# talkie.net
KiCad netlist of a schematic drawn in EAGLE
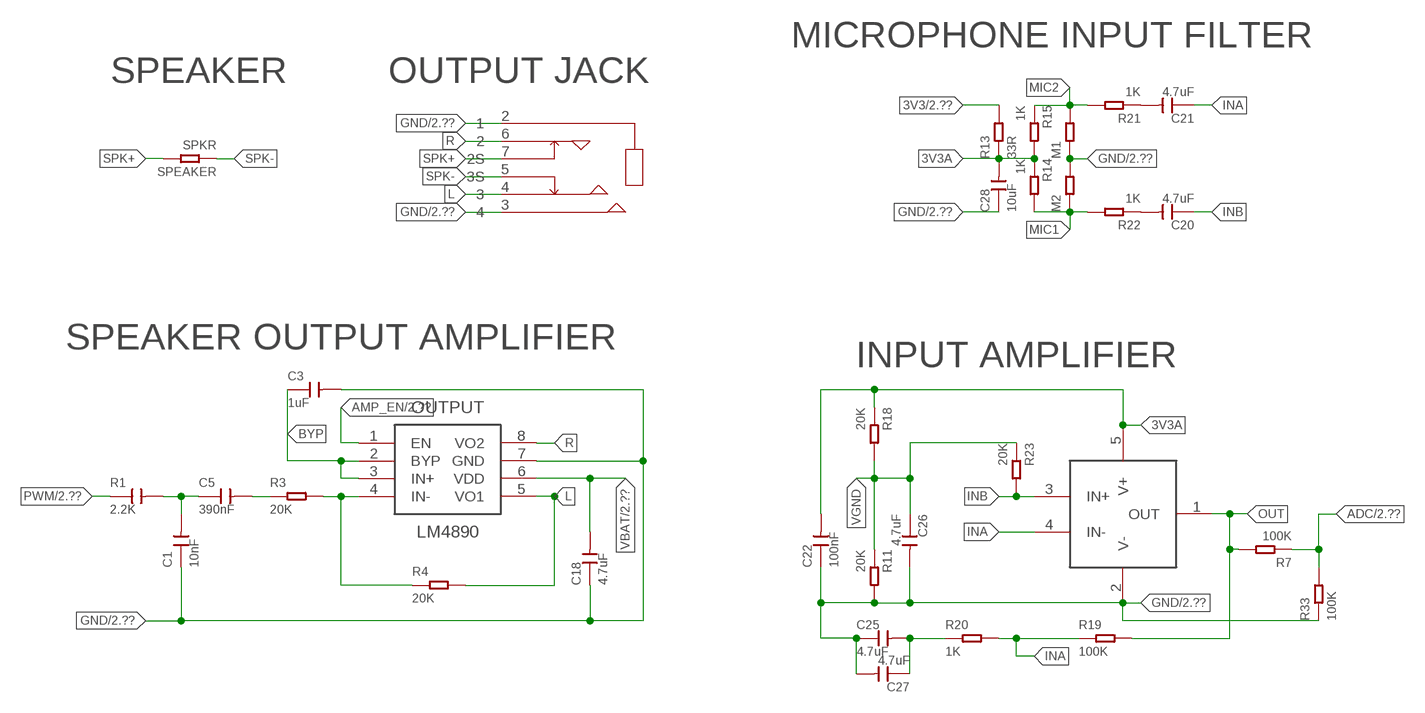
[diagram p0: schematic, sheet 1]
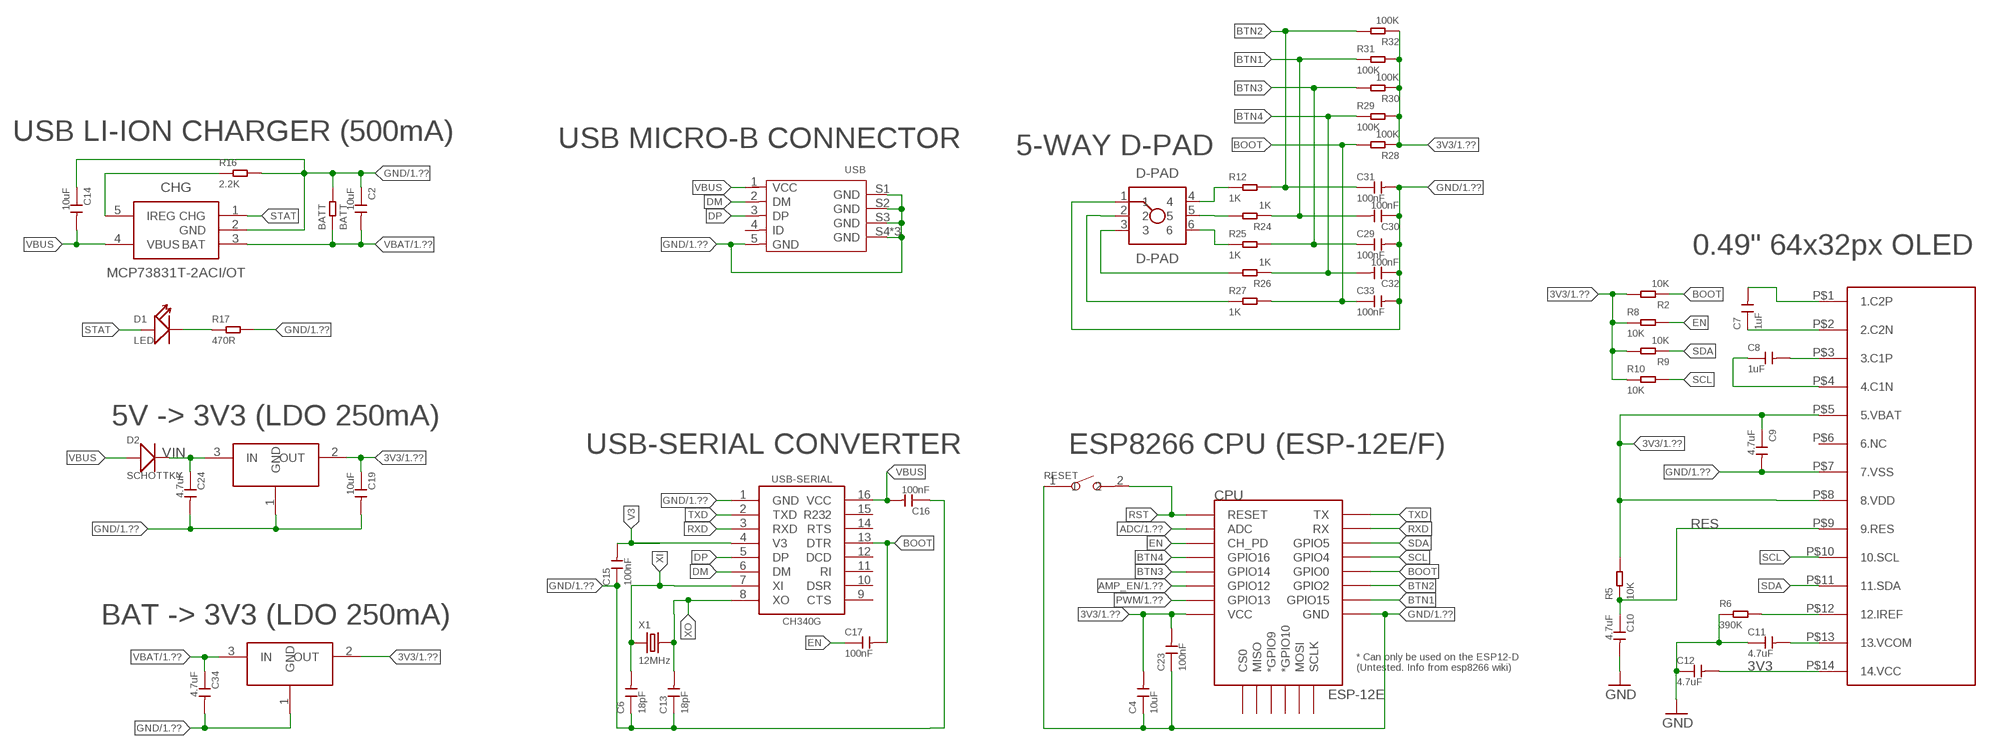
[diagram p1: schematic, sheet 2]

(export (version "E")
  (design (tool "Eeschema 10.0.6"))
  (components
    (comp (ref "C1")
      (value "10nF")
      (footprint "eagle-import:C0402")
      (fields (field (name "MPN") "CC0402KRX7R9BB103"))
      (libsource (lib "eagle-import") (part "CERAMIC-10NF-50V-10%-X7R(0402)"))
    )
    (comp (ref "C3")
      (value "1uF")
      (footprint "eagle-import:C0402")
      (fields (field (name "MPN") "CC0402KRX5R6BB105"))
      (libsource (lib "eagle-import") (part "CERAMIC-1UF-10V-10%-X5R(0402)"))
    )
    (comp (ref "C5")
      (value "390nF")
      (footprint "eagle-import:C0402")
      (fields (field (name "MPN") "CC0402KRX5R6BB474"))
      (libsource (lib "eagle-import") (part "CERAMIC-470NF-10V-10%-X5R(0402)"))
    )
    (comp (ref "C18")
      (value "4.7uF")
      (footprint "eagle-import:C0402")
      (fields (field (name "MPN") "CC0402MRX5R5BB475"))
      (libsource (lib "eagle-import") (part "CERAMIC-4.7UF-6.3V-20%-X5R(0402)"))
    )
    (comp (ref "C20")
      (value "4.7uF")
      (footprint "eagle-import:C0402")
      (fields (field (name "MPN") "CC0402MRX5R5BB475"))
      (libsource (lib "eagle-import") (part "CERAMIC-4.7UF-6.3V-20%-X5R(0402)"))
    )
    (comp (ref "C21")
      (value "4.7uF")
      (footprint "eagle-import:C0402")
      (fields (field (name "MPN") "CC0402MRX5R5BB475"))
      (libsource (lib "eagle-import") (part "CERAMIC-4.7UF-6.3V-20%-X5R(0402)"))
    )
    (comp (ref "C22")
      (value "100nF")
      (footprint "eagle-import:C0402")
      (fields (field (name "MPN") "CC0402KRX7R8BB104"))
      (libsource (lib "eagle-import") (part "CERAMIC-100NF-25V-10%-X7R(0402)"))
    )
    (comp (ref "C25")
      (value "4.7uF")
      (footprint "eagle-import:C0402")
      (fields (field (name "MPN") "CC0402MRX5R5BB475"))
      (libsource (lib "eagle-import") (part "CERAMIC-4.7UF-6.3V-20%-X5R(0402)"))
    )
    (comp (ref "C26")
      (value "4.7uF")
      (footprint "eagle-import:C0402")
      (fields (field (name "MPN") "CC0402MRX5R5BB475"))
      (libsource (lib "eagle-import") (part "CERAMIC-4.7UF-6.3V-20%-X5R(0402)"))
    )
    (comp (ref "C27")
      (value "4.7uF")
      (footprint "eagle-import:C0402")
      (fields (field (name "MPN") "CC0402MRX5R5BB475"))
      (libsource (lib "eagle-import") (part "CERAMIC-4.7UF-6.3V-20%-X5R(0402)"))
    )
    (comp (ref "C28")
      (value "10uF")
      (footprint "eagle-import:C0603")
      (fields (field (name "MPN") "CC0603KRX5R6BB106"))
      (libsource (lib "eagle-import") (part "CERAMIC-10UF-10V-10%-X5R(0603)"))
    )
    (comp (ref "JACK")
      (value "PJ-342")
      (footprint "eagle-import:PJ-342-6P")
      (libsource (lib "eagle-import") (part "PJ-342"))
    )
    (comp (ref "M1")
      (value "RES-1206")
      (footprint "eagle-import:R1206")
      (libsource (lib "eagle-import") (part "RES-1206"))
    )
    (comp (ref "M2")
      (value "RES-1206")
      (footprint "eagle-import:R1206")
      (libsource (lib "eagle-import") (part "RES-1206"))
    )
    (comp (ref "OUTPUT")
      (value "LM4890")
      (footprint "eagle-import:8-MSOP")
      (libsource (lib "eagle-import") (part "LM4890"))
    )
    (comp (ref "PREAMP")
      (value "MCP6001UT-I")
      (footprint "eagle-import:SOT-23-5")
      (libsource (lib "eagle-import") (part "MCP6001UT-I"))
    )
    (comp (ref "R1")
      (value "2.2K")
      (footprint "eagle-import:C0402")
      (fields (field (name "MPN") "CC0402KRX7R9BB103"))
      (libsource (lib "eagle-import") (part "CERAMIC-10NF-50V-10%-X7R(0402)"))
    )
    (comp (ref "R3")
      (value "20K")
      (footprint "eagle-import:R0402")
      (libsource (lib "eagle-import") (part "RES-0402"))
    )
    (comp (ref "R4")
      (value "20K")
      (footprint "eagle-import:R0402")
      (libsource (lib "eagle-import") (part "RES-0402"))
    )
    (comp (ref "R7")
      (value "100K")
      (footprint "eagle-import:R0402")
      (fields (field (name "MPN") "RC0402FR-07100KL"))
      (libsource (lib "eagle-import") (part "SMD-RES-100K-1%-1/16W(0402)"))
    )
    (comp (ref "R11")
      (value "20K")
      (footprint "eagle-import:R0402")
      (libsource (lib "eagle-import") (part "RES-0402"))
    )
    (comp (ref "R13")
      (value "33R")
      (footprint "eagle-import:R0402")
      (fields (field (name "MPN") "RC0402FR-0733RL"))
      (libsource (lib "eagle-import") (part "SMD-RES-33R-1%-1/16W(0402)"))
    )
    (comp (ref "R14")
      (value "1K")
      (footprint "eagle-import:R0402")
      (fields (field (name "MPN") "RC0402JR-071K5L"))
      (libsource (lib "eagle-import") (part "SMD-RES-1.5K-5%-1/16W(0402)"))
    )
    (comp (ref "R15")
      (value "1K")
      (footprint "eagle-import:R0402")
      (fields (field (name "MPN") "RC0402JR-071K5L"))
      (libsource (lib "eagle-import") (part "SMD-RES-1.5K-5%-1/16W(0402)"))
    )
    (comp (ref "R18")
      (value "20K")
      (footprint "eagle-import:R0402")
      (libsource (lib "eagle-import") (part "RES-0402"))
    )
    (comp (ref "R19")
      (value "100K")
      (footprint "eagle-import:R0402")
      (fields (field (name "MPN") "RC0402FR-07100KL"))
      (libsource (lib "eagle-import") (part "SMD-RES-100K-1%-1/16W(0402)"))
    )
    (comp (ref "R20")
      (value "1K")
      (footprint "eagle-import:R0402")
      (fields (field (name "MPN") "RC0402JR-071KL"))
      (libsource (lib "eagle-import") (part "SMD-RES-1K-5%-1/16W(0402)"))
    )
    (comp (ref "R21")
      (value "1K")
      (footprint "eagle-import:R0402")
      (fields (field (name "MPN") "RC0402JR-071K5L"))
      (libsource (lib "eagle-import") (part "SMD-RES-1.5K-5%-1/16W(0402)"))
    )
    (comp (ref "R22")
      (value "1K")
      (footprint "eagle-import:R0402")
      (fields (field (name "MPN") "RC0402JR-071K5L"))
      (libsource (lib "eagle-import") (part "SMD-RES-1.5K-5%-1/16W(0402)"))
    )
    (comp (ref "R23")
      (value "20K")
      (footprint "eagle-import:R0402")
      (libsource (lib "eagle-import") (part "RES-0402"))
    )
    (comp (ref "R33")
      (value "100K")
      (footprint "eagle-import:R0402")
      (fields (field (name "MPN") "RC0402FR-07100KL"))
      (libsource (lib "eagle-import") (part "SMD-RES-100K-1%-1/16W(0402)"))
    )
    (comp (ref "SPEAKER")
      (value "SPKR")
      (footprint "eagle-import:R1206")
      (libsource (lib "eagle-import") (part "RES-1206"))
    )
    (comp (ref "BATT")
      (value "BATT")
      (footprint "eagle-import:R1206")
      (libsource (lib "eagle-import") (part "RES-1206"))
    )
    (comp (ref "C2")
      (value "10uF")
      (footprint "eagle-import:C0603")
      (fields (field (name "MPN") "CC0603KRX5R6BB106"))
      (libsource (lib "eagle-import") (part "CERAMIC-10UF-10V-10%-X5R(0603)"))
    )
    (comp (ref "C4")
      (value "10uF")
      (footprint "eagle-import:C0603")
      (fields (field (name "MPN") "CC0603KRX5R6BB475"))
      (libsource (lib "eagle-import") (part "CERAMIC-4.7UF-10V-10%-X5R(0603)"))
    )
    (comp (ref "C6")
      (value "18pF")
      (footprint "eagle-import:C0402")
      (fields (field (name "MPN") "CC0402JRNPO9BN180"))
      (libsource (lib "eagle-import") (part "CERAMIC-18PF-50V-5%-NPO(0402)"))
    )
    (comp (ref "C7")
      (value "1uF")
      (footprint "eagle-import:C0402")
      (fields (field (name "MPN") "CC0402KRX5R6BB105"))
      (libsource (lib "eagle-import") (part "CERAMIC-1UF-10V-10%-X5R(0402)"))
    )
    (comp (ref "C8")
      (value "1uF")
      (footprint "eagle-import:C0402")
      (fields (field (name "MPN") "CC0402KRX5R6BB105"))
      (libsource (lib "eagle-import") (part "CERAMIC-1UF-10V-10%-X5R(0402)"))
    )
    (comp (ref "C9")
      (value "4.7uF")
      (footprint "eagle-import:C0402")
      (fields (field (name "MPN") "CC0402MRX5R5BB475"))
      (libsource (lib "eagle-import") (part "CERAMIC-4.7UF-6.3V-20%-X5R(0402)"))
    )
    (comp (ref "C10")
      (value "4.7uF")
      (footprint "eagle-import:C0402")
      (fields (field (name "MPN") "CC0402MRX5R5BB475"))
      (libsource (lib "eagle-import") (part "CERAMIC-4.7UF-6.3V-20%-X5R(0402)"))
    )
    (comp (ref "C11")
      (value "4.7uF")
      (footprint "eagle-import:C0402")
      (fields (field (name "MPN") "CC0402MRX5R5BB475"))
      (libsource (lib "eagle-import") (part "CERAMIC-4.7UF-6.3V-20%-X5R(0402)"))
    )
    (comp (ref "C12")
      (value "4.7uF")
      (footprint "eagle-import:C0402")
      (fields (field (name "MPN") "CC0402MRX5R5BB475"))
      (libsource (lib "eagle-import") (part "CERAMIC-4.7UF-6.3V-20%-X5R(0402)"))
    )
    (comp (ref "C13")
      (value "18pF")
      (footprint "eagle-import:C0402")
      (fields (field (name "MPN") "CC0402JRNPO9BN180"))
      (libsource (lib "eagle-import") (part "CERAMIC-18PF-50V-5%-NPO(0402)"))
    )
    (comp (ref "C14")
      (value "10uF")
      (footprint "eagle-import:C0603")
      (fields (field (name "MPN") "CC0603KRX5R6BB106"))
      (libsource (lib "eagle-import") (part "CERAMIC-10UF-10V-10%-X5R(0603)"))
    )
    (comp (ref "C15")
      (value "100nF")
      (footprint "eagle-import:C0402")
      (fields (field (name "MPN") "CC0402KRX7R8BB104"))
      (libsource (lib "eagle-import") (part "CERAMIC-100NF-25V-10%-X7R(0402)"))
    )
    (comp (ref "C16")
      (value "100nF")
      (footprint "eagle-import:C0402")
      (fields (field (name "MPN") "CC0402KRX7R8BB104"))
      (libsource (lib "eagle-import") (part "CERAMIC-100NF-25V-10%-X7R(0402)"))
    )
    (comp (ref "C17")
      (value "100nF")
      (footprint "eagle-import:C0402")
      (fields (field (name "MPN") "CC0402KRX7R8BB104"))
      (libsource (lib "eagle-import") (part "CERAMIC-100NF-25V-10%-X7R(0402)"))
    )
    (comp (ref "C19")
      (value "10uF")
      (footprint "eagle-import:C0603")
      (fields (field (name "MPN") "CC0603KRX5R6BB106"))
      (libsource (lib "eagle-import") (part "CERAMIC-10UF-10V-10%-X5R(0603)"))
    )
    (comp (ref "C23")
      (value "100nF")
      (footprint "eagle-import:C0402")
      (fields (field (name "MPN") "CC0402KRX7R8BB104"))
      (libsource (lib "eagle-import") (part "CERAMIC-100NF-25V-10%-X7R(0402)"))
    )
    (comp (ref "C24")
      (value "4.7uF")
      (footprint "eagle-import:C0402")
      (fields (field (name "MPN") "CC0402MRX5R5BB475"))
      (libsource (lib "eagle-import") (part "CERAMIC-4.7UF-6.3V-20%-X5R(0402)"))
    )
    (comp (ref "C29")
      (value "100nF")
      (footprint "eagle-import:C0402")
      (fields (field (name "MPN") "CC0402KRX7R8BB104"))
      (libsource (lib "eagle-import") (part "CERAMIC-100NF-25V-10%-X7R(0402)"))
    )
    (comp (ref "C30")
      (value "100nF")
      (footprint "eagle-import:C0402")
      (fields (field (name "MPN") "CC0402KRX7R8BB104"))
      (libsource (lib "eagle-import") (part "CERAMIC-100NF-25V-10%-X7R(0402)"))
    )
    (comp (ref "C31")
      (value "100nF")
      (footprint "eagle-import:C0402")
      (fields (field (name "MPN") "CC0402KRX7R8BB104"))
      (libsource (lib "eagle-import") (part "CERAMIC-100NF-25V-10%-X7R(0402)"))
    )
    (comp (ref "C32")
      (value "100nF")
      (footprint "eagle-import:C0402")
      (fields (field (name "MPN") "CC0402KRX7R8BB104"))
      (libsource (lib "eagle-import") (part "CERAMIC-100NF-25V-10%-X7R(0402)"))
    )
    (comp (ref "C33")
      (value "100nF")
      (footprint "eagle-import:C0402")
      (fields (field (name "MPN") "CC0402KRX7R8BB104"))
      (libsource (lib "eagle-import") (part "CERAMIC-100NF-25V-10%-X7R(0402)"))
    )
    (comp (ref "C34")
      (value "4.7uF")
      (footprint "eagle-import:C0402")
      (fields (field (name "MPN") "CC0402MRX5R5BB475"))
      (libsource (lib "eagle-import") (part "CERAMIC-4.7UF-6.3V-20%-X5R(0402)"))
    )
    (comp (ref "CHG")
      (value "MCP73831T-2ACI/OT")
      (footprint "eagle-import:SOT-23-5")
      (libsource (lib "eagle-import") (part "MCP73831T-2ACI/OT"))
    )
    (comp (ref "CPU")
      (value "ESP-12E")
      (footprint "eagle-import:ESP12E-SMD")
      (libsource (lib "eagle-import") (part "ESP12ESMD"))
    )
    (comp (ref "D-PAD")
      (value "D-PAD")
      (footprint "eagle-import:DPAD-10X10")
      (libsource (lib "eagle-import") (part "D-PAD"))
    )
    (comp (ref "D1")
      (value "LED")
      (footprint "eagle-import:LED-0402")
      (fields (field (name "MPN") "16-219A/T2D-AR2T1QY/3T"))
      (libsource (lib "eagle-import") (part "SMD-LED-YELLOW-DIFFUSED-PURE-WHITE(0402)"))
    )
    (comp (ref "D2")
      (value "SCHOTTKY")
      (footprint "eagle-import:SOD-123")
      (fields (field (name "MPN") "MBR0520LT1G"))
      (libsource (lib "eagle-import") (part "SMD-DIODE-SCHOTTKY-20V-500MA(SOD-123)"))
    )
    (comp (ref "LDO1")
      (value "MCP1700T")
      (footprint "eagle-import:SOT-23-3")
      (libsource (lib "eagle-import") (part "MCP1700T"))
    )
    (comp (ref "LDO2")
      (value "MCP1700T-3302E")
      (footprint "eagle-import:SOT-23-3")
      (libsource (lib "eagle-import") (part "MCP1700T"))
    )
    (comp (ref "OLED")
      (value "ER-OLED0.49")
      (footprint "eagle-import:ER-OLED0.49")
      (libsource (lib "eagle-import") (part "ER-OLED0.49"))
    )
    (comp (ref "R2")
      (value "10K")
      (footprint "eagle-import:R0402")
      (libsource (lib "eagle-import") (part "RES-0402"))
    )
    (comp (ref "R5")
      (value "10K")
      (footprint "eagle-import:R0402")
      (libsource (lib "eagle-import") (part "RES-0402"))
    )
    (comp (ref "R6")
      (value "390K")
      (footprint "eagle-import:R0402")
      (libsource (lib "eagle-import") (part "RES-0402"))
    )
    (comp (ref "R8")
      (value "10K")
      (footprint "eagle-import:R0402")
      (libsource (lib "eagle-import") (part "RES-0402"))
    )
    (comp (ref "R9")
      (value "10K")
      (footprint "eagle-import:R0402")
      (libsource (lib "eagle-import") (part "RES-0402"))
    )
    (comp (ref "R10")
      (value "10K")
      (footprint "eagle-import:R0402")
      (libsource (lib "eagle-import") (part "RES-0402"))
    )
    (comp (ref "R12")
      (value "1K")
      (footprint "eagle-import:R0402")
      (fields (field (name "MPN") "RC0402JR-071K5L"))
      (libsource (lib "eagle-import") (part "SMD-RES-1.5K-5%-1/16W(0402)"))
    )
    (comp (ref "R16")
      (value "2.2K")
      (footprint "eagle-import:R0402")
      (fields (field (name "MPN") "RC0402JR-072K2L"))
      (libsource (lib "eagle-import") (part "SMD-RES-2.2K-5%-1/16W(0402)"))
    )
    (comp (ref "R17")
      (value "470R")
      (footprint "eagle-import:R0402")
      (fields (field (name "MPN") "RC0402FR-07470RL"))
      (libsource (lib "eagle-import") (part "SMD-RES-470R-1%-1/16W(0402)"))
    )
    (comp (ref "R24")
      (value "1K")
      (footprint "eagle-import:R0402")
      (fields (field (name "MPN") "RC0402JR-071K5L"))
      (libsource (lib "eagle-import") (part "SMD-RES-1.5K-5%-1/16W(0402)"))
    )
    (comp (ref "R25")
      (value "1K")
      (footprint "eagle-import:R0402")
      (fields (field (name "MPN") "RC0402JR-071K5L"))
      (libsource (lib "eagle-import") (part "SMD-RES-1.5K-5%-1/16W(0402)"))
    )
    (comp (ref "R26")
      (value "1K")
      (footprint "eagle-import:R0402")
      (fields (field (name "MPN") "RC0402JR-071K5L"))
      (libsource (lib "eagle-import") (part "SMD-RES-1.5K-5%-1/16W(0402)"))
    )
    (comp (ref "R27")
      (value "1K")
      (footprint "eagle-import:R0402")
      (fields (field (name "MPN") "RC0402JR-071K5L"))
      (libsource (lib "eagle-import") (part "SMD-RES-1.5K-5%-1/16W(0402)"))
    )
    (comp (ref "R28")
      (value "100K")
      (footprint "eagle-import:R0402")
      (fields (field (name "MPN") "RC0402FR-07100KL"))
      (libsource (lib "eagle-import") (part "SMD-RES-100K-1%-1/16W(0402)"))
    )
    (comp (ref "R29")
      (value "100K")
      (footprint "eagle-import:R0402")
      (fields (field (name "MPN") "RC0402FR-07100KL"))
      (libsource (lib "eagle-import") (part "SMD-RES-100K-1%-1/16W(0402)"))
    )
    (comp (ref "R30")
      (value "100K")
      (footprint "eagle-import:R0402")
      (fields (field (name "MPN") "RC0402FR-07100KL"))
      (libsource (lib "eagle-import") (part "SMD-RES-100K-1%-1/16W(0402)"))
    )
    (comp (ref "R31")
      (value "100K")
      (footprint "eagle-import:R0402")
      (fields (field (name "MPN") "RC0402FR-07100KL"))
      (libsource (lib "eagle-import") (part "SMD-RES-100K-1%-1/16W(0402)"))
    )
    (comp (ref "R32")
      (value "100K")
      (footprint "eagle-import:R0402")
      (fields (field (name "MPN") "RC0402FR-07100KL"))
      (libsource (lib "eagle-import") (part "SMD-RES-100K-1%-1/16W(0402)"))
    )
    (comp (ref "RESET")
      (value "SMD-BUTTON(2P-3.0X2.5X1.2+0.4MM)-B3U-1000P-2P-SMD")
      (footprint "eagle-import:SW2-2.6-3.0X2.5X1.2+0.4MM")
      (libsource (lib "eagle-import") (part "SMD-BUTTON(2P-3.0X2.5X1.2+0.4MM)-B3U-1000P-2P-SMD"))
    )
    (comp (ref "USB")
      (value "MICRO-USB-SMD-B-WITHOUT-POST-W/P(ST-USB-001G)")
      (footprint "eagle-import:MICRO-USB5+4P-SMD-0.65-B")
      (fields (field (name "MPN") "ST-USB-001G"))
      (libsource (lib "eagle-import") (part "MICRO-USB-SMD-B-WITHOUT-POST-W/P(ST-USB-001G)"))
    )
    (comp (ref "USB-SERIAL")
      (value "CH340G")
      (footprint "eagle-import:16-SSOP")
      (libsource (lib "eagle-import") (part "CH340G"))
    )
    (comp (ref "X1")
      (value "12MHz")
      (footprint "eagle-import:X4-SMD-3.2X2.5X0.7MM")
      (libsource (lib "eagle-import") (part "CRYSTAL'3225'"))
    )
  )
  (nets
    (net (code "1") (name "3V3") (class "Default")
      (node (ref "C12") (pin "2") (pinfunction "2_2") (pintype "passive"))
      (node (ref "C19") (pin "1") (pinfunction "1_1") (pintype "passive"))
      (node (ref "C23") (pin "2") (pinfunction "2_2") (pintype "passive"))
      (node (ref "C4") (pin "2") (pinfunction "2_2") (pintype "passive"))
      (node (ref "C9") (pin "1") (pinfunction "1_1") (pintype "passive"))
      (node (ref "CPU") (pin "VCC") (pinfunction "VCC_VCC") (pintype "bidirectional"))
      (node (ref "LDO1") (pin "2") (pinfunction "OUT_2") (pintype "bidirectional"))
      (node (ref "LDO2") (pin "2") (pinfunction "OUT_2") (pintype "bidirectional"))
      (node (ref "OLED") (pin "P$14") (pinfunction "14.VCC_P$14") (pintype "bidirectional"))
      (node (ref "OLED") (pin "P$5") (pinfunction "5.VBAT_P$5") (pintype "bidirectional"))
      (node (ref "OLED") (pin "P$8") (pinfunction "8.VDD_P$8") (pintype "bidirectional"))
      (node (ref "R10") (pin "1") (pinfunction "1_1") (pintype "passive"))
      (node (ref "R13") (pin "2") (pinfunction "2_2") (pintype "passive"))
      (node (ref "R2") (pin "2") (pinfunction "2_2") (pintype "passive"))
      (node (ref "R28") (pin "1") (pinfunction "1_1") (pintype "passive"))
      (node (ref "R29") (pin "2") (pinfunction "2_2") (pintype "passive"))
      (node (ref "R30") (pin "1") (pinfunction "1_1") (pintype "passive"))
      (node (ref "R31") (pin "2") (pinfunction "2_2") (pintype "passive"))
      (node (ref "R32") (pin "1") (pinfunction "1_1") (pintype "passive"))
      (node (ref "R5") (pin "2") (pinfunction "2_2") (pintype "passive"))
      (node (ref "R8") (pin "1") (pinfunction "1_1") (pintype "passive"))
      (node (ref "R9") (pin "2") (pinfunction "2_2") (pintype "passive"))
    )
    (net (code "2") (name "3V3A") (class "Default")
      (node (ref "C22") (pin "2") (pinfunction "2_2") (pintype "passive"))
      (node (ref "C28") (pin "2") (pinfunction "2_2") (pintype "passive"))
      (node (ref "PREAMP") (pin "5") (pinfunction "V+_5") (pintype "bidirectional"))
      (node (ref "R13") (pin "1") (pinfunction "1_1") (pintype "passive"))
      (node (ref "R14") (pin "1") (pinfunction "1_1") (pintype "passive"))
      (node (ref "R15") (pin "2") (pinfunction "2_2") (pintype "passive"))
      (node (ref "R18") (pin "1") (pinfunction "1_1") (pintype "passive"))
    )
    (net (code "3") (name "ADC") (class "Default")
      (node (ref "CPU") (pin "ADC") (pinfunction "ADC_ADC") (pintype "bidirectional"))
      (node (ref "R33") (pin "2") (pinfunction "2_2") (pintype "passive"))
      (node (ref "R7") (pin "1") (pinfunction "1_1") (pintype "passive"))
    )
    (net (code "4") (name "AMP_EN") (class "Default")
      (node (ref "CPU") (pin "GPIO12") (pinfunction "GPIO12_GPIO12") (pintype "bidirectional"))
      (node (ref "OUTPUT") (pin "1") (pinfunction "EN_1") (pintype "bidirectional"))
    )
    (net (code "5") (name "BOOT") (class "Default")
      (node (ref "C17") (pin "2") (pinfunction "2_2") (pintype "passive"))
      (node (ref "C33") (pin "1") (pinfunction "1_1") (pintype "passive"))
      (node (ref "CPU") (pin "GPIO0") (pinfunction "GPIO0_GPIO0") (pintype "bidirectional"))
      (node (ref "R2") (pin "1") (pinfunction "1_1") (pintype "passive"))
      (node (ref "R27") (pin "2") (pinfunction "2_2") (pintype "passive"))
      (node (ref "R28") (pin "2") (pinfunction "2_2") (pintype "passive"))
      (node (ref "USB-SERIAL") (pin "13") (pinfunction "DTR_13") (pintype "bidirectional"))
    )
    (net (code "6") (name "BTN1") (class "Default")
      (node (ref "C30") (pin "2") (pinfunction "2_2") (pintype "passive"))
      (node (ref "CPU") (pin "GPIO15") (pinfunction "GPIO15_GPIO15") (pintype "bidirectional"))
      (node (ref "R24") (pin "1") (pinfunction "1_1") (pintype "passive"))
      (node (ref "R31") (pin "1") (pinfunction "1_1") (pintype "passive"))
    )
    (net (code "7") (name "BTN2") (class "Default")
      (node (ref "C31") (pin "1") (pinfunction "1_1") (pintype "passive"))
      (node (ref "CPU") (pin "GPIO2") (pinfunction "GPIO2_GPIO2") (pintype "bidirectional"))
      (node (ref "R12") (pin "2") (pinfunction "2_2") (pintype "passive"))
      (node (ref "R32") (pin "2") (pinfunction "2_2") (pintype "passive"))
    )
    (net (code "8") (name "BTN3") (class "Default")
      (node (ref "C29") (pin "1") (pinfunction "1_1") (pintype "passive"))
      (node (ref "CPU") (pin "GPIO14") (pinfunction "GPIO14_GPIO14") (pintype "bidirectional"))
      (node (ref "R25") (pin "2") (pinfunction "2_2") (pintype "passive"))
      (node (ref "R30") (pin "2") (pinfunction "2_2") (pintype "passive"))
    )
    (net (code "9") (name "BTN4") (class "Default")
      (node (ref "C32") (pin "2") (pinfunction "2_2") (pintype "passive"))
      (node (ref "CPU") (pin "GPIO16") (pinfunction "GPIO16_GPIO16") (pintype "bidirectional"))
      (node (ref "R26") (pin "1") (pinfunction "1_1") (pintype "passive"))
      (node (ref "R29") (pin "1") (pinfunction "1_1") (pintype "passive"))
    )
    (net (code "10") (name "BYP") (class "Default")
      (node (ref "C3") (pin "1") (pinfunction "1_1") (pintype "passive"))
      (node (ref "OUTPUT") (pin "2") (pinfunction "BYP_2") (pintype "bidirectional"))
      (node (ref "OUTPUT") (pin "3") (pinfunction "IN+_3") (pintype "bidirectional"))
    )
    (net (code "11") (name "DM") (class "Default")
      (node (ref "USB") (pin "2") (pinfunction "DM_2") (pintype "bidirectional"))
      (node (ref "USB-SERIAL") (pin "6") (pinfunction "DM_6") (pintype "bidirectional"))
    )
    (net (code "12") (name "DP") (class "Default")
      (node (ref "USB") (pin "3") (pinfunction "DP_3") (pintype "bidirectional"))
      (node (ref "USB-SERIAL") (pin "5") (pinfunction "DP_5") (pintype "bidirectional"))
    )
    (net (code "13") (name "EN") (class "Default")
      (node (ref "C17") (pin "1") (pinfunction "1_1") (pintype "passive"))
      (node (ref "CPU") (pin "CH_PD") (pinfunction "CH_PD_CH_PD") (pintype "bidirectional"))
      (node (ref "R8") (pin "2") (pinfunction "2_2") (pintype "passive"))
    )
    (net (code "14") (name "GND") (class "Default")
      (node (ref "BATT") (pin "2") (pinfunction "2_2") (pintype "passive"))
      (node (ref "C1") (pin "1") (pinfunction "1_1") (pintype "passive"))
      (node (ref "C10") (pin "2") (pinfunction "2_2") (pintype "passive"))
      (node (ref "C11") (pin "1") (pinfunction "1_1") (pintype "passive"))
      (node (ref "C12") (pin "1") (pinfunction "1_1") (pintype "passive"))
      (node (ref "C13") (pin "1") (pinfunction "1_1") (pintype "passive"))
      (node (ref "C14") (pin "1") (pinfunction "1_1") (pintype "passive"))
      (node (ref "C15") (pin "1") (pinfunction "1_1") (pintype "passive"))
      (node (ref "C16") (pin "1") (pinfunction "1_1") (pintype "passive"))
      (node (ref "C18") (pin "1") (pinfunction "1_1") (pintype "passive"))
      (node (ref "C19") (pin "2") (pinfunction "2_2") (pintype "passive"))
      (node (ref "C2") (pin "1") (pinfunction "1_1") (pintype "passive"))
      (node (ref "C22") (pin "1") (pinfunction "1_1") (pintype "passive"))
      (node (ref "C23") (pin "1") (pinfunction "1_1") (pintype "passive"))
      (node (ref "C24") (pin "2") (pinfunction "2_2") (pintype "passive"))
      (node (ref "C25") (pin "1") (pinfunction "1_1") (pintype "passive"))
      (node (ref "C26") (pin "2") (pinfunction "2_2") (pintype "passive"))
      (node (ref "C27") (pin "2") (pinfunction "2_2") (pintype "passive"))
      (node (ref "C28") (pin "1") (pinfunction "1_1") (pintype "passive"))
      (node (ref "C29") (pin "2") (pinfunction "2_2") (pintype "passive"))
      (node (ref "C3") (pin "2") (pinfunction "2_2") (pintype "passive"))
      (node (ref "C30") (pin "1") (pinfunction "1_1") (pintype "passive"))
      (node (ref "C31") (pin "2") (pinfunction "2_2") (pintype "passive"))
      (node (ref "C32") (pin "1") (pinfunction "1_1") (pintype "passive"))
      (node (ref "C33") (pin "2") (pinfunction "2_2") (pintype "passive"))
      (node (ref "C34") (pin "2") (pinfunction "2_2") (pintype "passive"))
      (node (ref "C4") (pin "1") (pinfunction "1_1") (pintype "passive"))
      (node (ref "C6") (pin "1") (pinfunction "1_1") (pintype "passive"))
      (node (ref "C9") (pin "2") (pinfunction "2_2") (pintype "passive"))
      (node (ref "CHG") (pin "2") (pinfunction "GND_2") (pintype "bidirectional"))
      (node (ref "CPU") (pin "GND") (pinfunction "GND_GND") (pintype "bidirectional"))
      (node (ref "D-PAD") (pin "1") (pinfunction "1_1") (pintype "bidirectional"))
      (node (ref "JACK") (pin "2") (pinfunction "1_2") (pintype "bidirectional"))
      (node (ref "JACK") (pin "3") (pinfunction "4_3") (pintype "bidirectional"))
      (node (ref "LDO1") (pin "1") (pinfunction "GND_1") (pintype "bidirectional"))
      (node (ref "LDO2") (pin "1") (pinfunction "GND_1") (pintype "bidirectional"))
      (node (ref "M1") (pin "1") (pinfunction "1_1") (pintype "passive"))
      (node (ref "M2") (pin "2") (pinfunction "2_2") (pintype "passive"))
      (node (ref "OLED") (pin "P$7") (pinfunction "7.VSS_P$7") (pintype "bidirectional"))
      (node (ref "OUTPUT") (pin "7") (pinfunction "GND_7") (pintype "bidirectional"))
      (node (ref "PREAMP") (pin "2") (pinfunction "V-_2") (pintype "bidirectional"))
      (node (ref "R11") (pin "2") (pinfunction "2_2") (pintype "passive"))
      (node (ref "R16") (pin "2") (pinfunction "2_2") (pintype "passive"))
      (node (ref "R17") (pin "2") (pinfunction "2_2") (pintype "passive"))
      (node (ref "R33") (pin "1") (pinfunction "1_1") (pintype "passive"))
      (node (ref "R6") (pin "1") (pinfunction "1_1") (pintype "passive"))
      (node (ref "RESET") (pin "1") (pinfunction "1_1") (pintype "bidirectional"))
      (node (ref "USB") (pin "5") (pinfunction "GND_5") (pintype "bidirectional"))
      (node (ref "USB") (pin "S1") (pinfunction "GND_S1") (pintype "bidirectional"))
      (node (ref "USB") (pin "S2") (pinfunction "GND_S2") (pintype "bidirectional"))
      (node (ref "USB") (pin "S3") (pinfunction "GND_S3") (pintype "bidirectional"))
      (node (ref "USB") (pin "S4") (pinfunction "GND_S4") (pintype "bidirectional"))
      (node (ref "USB") (pin "S5") (pinfunction "GND_S5") (pintype "bidirectional"))
      (node (ref "USB") (pin "S6") (pinfunction "GND_S6") (pintype "bidirectional"))
      (node (ref "USB-SERIAL") (pin "1") (pinfunction "GND_1") (pintype "bidirectional"))
    )
    (net (code "15") (name "INA") (class "Default")
      (node (ref "C21") (pin "1") (pinfunction "1_1") (pintype "passive"))
      (node (ref "PREAMP") (pin "4") (pinfunction "IN-_4") (pintype "bidirectional"))
      (node (ref "R19") (pin "1") (pinfunction "1_1") (pintype "passive"))
      (node (ref "R20") (pin "2") (pinfunction "2_2") (pintype "passive"))
    )
    (net (code "16") (name "INB") (class "Default")
      (node (ref "C20") (pin "1") (pinfunction "1_1") (pintype "passive"))
      (node (ref "PREAMP") (pin "3") (pinfunction "IN+_3") (pintype "bidirectional"))
      (node (ref "R23") (pin "2") (pinfunction "2_2") (pintype "passive"))
    )
    (net (code "17") (name "L") (class "Default")
      (node (ref "JACK") (pin "4") (pinfunction "3_4") (pintype "bidirectional"))
      (node (ref "OUTPUT") (pin "5") (pinfunction "VO1_5") (pintype "bidirectional"))
      (node (ref "R4") (pin "2") (pinfunction "2_2") (pintype "passive"))
    )
    (net (code "18") (name "MIC1") (class "Default")
      (node (ref "M2") (pin "1") (pinfunction "1_1") (pintype "passive"))
      (node (ref "R14") (pin "2") (pinfunction "2_2") (pintype "passive"))
      (node (ref "R22") (pin "2") (pinfunction "2_2") (pintype "passive"))
    )
    (net (code "19") (name "MIC2") (class "Default")
      (node (ref "M1") (pin "2") (pinfunction "2_2") (pintype "passive"))
      (node (ref "R15") (pin "1") (pinfunction "1_1") (pintype "passive"))
      (node (ref "R21") (pin "2") (pinfunction "2_2") (pintype "passive"))
    )
    (net (code "20") (name "Net-(C1-Pad2)") (class "Default")
      (node (ref "C1") (pin "2") (pinfunction "2_2") (pintype "passive"))
      (node (ref "C5") (pin "1") (pinfunction "1_1") (pintype "passive"))
      (node (ref "R1") (pin "2") (pinfunction "2_2") (pintype "passive"))
    )
    (net (code "21") (name "Net-(C5-Pad2)") (class "Default")
      (node (ref "C5") (pin "2") (pinfunction "2_2") (pintype "passive"))
      (node (ref "R3") (pin "1") (pinfunction "1_1") (pintype "passive"))
    )
    (net (code "22") (name "Net-(C20-Pad2)") (class "Default")
      (node (ref "C20") (pin "2") (pinfunction "2_2") (pintype "passive"))
      (node (ref "R22") (pin "1") (pinfunction "1_1") (pintype "passive"))
    )
    (net (code "23") (name "Net-(C21-Pad2)") (class "Default")
      (node (ref "C21") (pin "2") (pinfunction "2_2") (pintype "passive"))
      (node (ref "R21") (pin "1") (pinfunction "1_1") (pintype "passive"))
    )
    (net (code "24") (name "Net-(C25-Pad2)") (class "Default")
      (node (ref "C25") (pin "2") (pinfunction "2_2") (pintype "passive"))
      (node (ref "C27") (pin "1") (pinfunction "1_1") (pintype "passive"))
      (node (ref "R20") (pin "1") (pinfunction "1_1") (pintype "passive"))
    )
    (net (code "25") (name "Net-(CHG-IREG)") (class "Default")
      (node (ref "CHG") (pin "5") (pinfunction "IREG_5") (pintype "bidirectional"))
      (node (ref "R16") (pin "1") (pinfunction "1_1") (pintype "passive"))
    )
    (net (code "26") (name "Net-(D-PAD-Pad2)") (class "Default")
      (node (ref "D-PAD") (pin "2") (pinfunction "2_2") (pintype "bidirectional"))
      (node (ref "R27") (pin "1") (pinfunction "1_1") (pintype "passive"))
    )
    (net (code "27") (name "Net-(D-PAD-Pad3)") (class "Default")
      (node (ref "D-PAD") (pin "3") (pinfunction "3_3") (pintype "bidirectional"))
      (node (ref "R26") (pin "2") (pinfunction "2_2") (pintype "passive"))
    )
    (net (code "28") (name "Net-(D-PAD-Pad4)") (class "Default")
      (node (ref "D-PAD") (pin "4") (pinfunction "4_4") (pintype "bidirectional"))
      (node (ref "R12") (pin "1") (pinfunction "1_1") (pintype "passive"))
    )
    (net (code "29") (name "Net-(D-PAD-Pad5)") (class "Default")
      (node (ref "D-PAD") (pin "5") (pinfunction "5_5") (pintype "bidirectional"))
      (node (ref "R24") (pin "2") (pinfunction "2_2") (pintype "passive"))
    )
    (net (code "30") (name "Net-(D-PAD-Pad6)") (class "Default")
      (node (ref "D-PAD") (pin "6") (pinfunction "6_6") (pintype "bidirectional"))
      (node (ref "R25") (pin "1") (pinfunction "1_1") (pintype "passive"))
    )
    (net (code "31") (name "Net-(D1-Pad-)") (class "Default")
      (node (ref "D1") (pin "-") (pinfunction "-_-") (pintype "passive"))
      (node (ref "R17") (pin "1") (pinfunction "1_1") (pintype "passive"))
    )
    (net (code "32") (name "Net-(OLED-1.C2P)") (class "Default")
      (node (ref "C7") (pin "2") (pinfunction "2_2") (pintype "passive"))
      (node (ref "OLED") (pin "P$1") (pinfunction "1.C2P_P$1") (pintype "bidirectional"))
    )
    (net (code "33") (name "Net-(OLED-2.C2N)") (class "Default")
      (node (ref "C7") (pin "1") (pinfunction "1_1") (pintype "passive"))
      (node (ref "OLED") (pin "P$2") (pinfunction "2.C2N_P$2") (pintype "bidirectional"))
    )
    (net (code "34") (name "Net-(OLED-3.C1P)") (class "Default")
      (node (ref "C8") (pin "2") (pinfunction "2_2") (pintype "passive"))
      (node (ref "OLED") (pin "P$3") (pinfunction "3.C1P_P$3") (pintype "bidirectional"))
    )
    (net (code "35") (name "Net-(OLED-4.C1N)") (class "Default")
      (node (ref "C8") (pin "1") (pinfunction "1_1") (pintype "passive"))
      (node (ref "OLED") (pin "P$4") (pinfunction "4.C1N_P$4") (pintype "bidirectional"))
    )
    (net (code "36") (name "Net-(OLED-12.IREF)") (class "Default")
      (node (ref "OLED") (pin "P$12") (pinfunction "12.IREF_P$12") (pintype "bidirectional"))
      (node (ref "R6") (pin "2") (pinfunction "2_2") (pintype "passive"))
    )
    (net (code "37") (name "Net-(OLED-13.VCOM)") (class "Default")
      (node (ref "C11") (pin "2") (pinfunction "2_2") (pintype "passive"))
      (node (ref "OLED") (pin "P$13") (pinfunction "13.VCOM_P$13") (pintype "bidirectional"))
    )
    (net (code "38") (name "Net-(OUTPUT-IN-)") (class "Default")
      (node (ref "OUTPUT") (pin "4") (pinfunction "IN-_4") (pintype "bidirectional"))
      (node (ref "R3") (pin "2") (pinfunction "2_2") (pintype "passive"))
      (node (ref "R4") (pin "1") (pinfunction "1_1") (pintype "passive"))
    )
    (net (code "39") (name "OUT") (class "Default")
      (node (ref "PREAMP") (pin "1") (pinfunction "OUT_1") (pintype "bidirectional"))
      (node (ref "R19") (pin "2") (pinfunction "2_2") (pintype "passive"))
      (node (ref "R7") (pin "2") (pinfunction "2_2") (pintype "passive"))
    )
    (net (code "40") (name "PWM") (class "Default")
      (node (ref "CPU") (pin "GPIO13") (pinfunction "GPIO13_GPIO13") (pintype "bidirectional"))
      (node (ref "R1") (pin "1") (pinfunction "1_1") (pintype "passive"))
    )
    (net (code "41") (name "R") (class "Default")
      (node (ref "JACK") (pin "6") (pinfunction "2_6") (pintype "bidirectional"))
      (node (ref "OUTPUT") (pin "8") (pinfunction "VO2_8") (pintype "bidirectional"))
    )
    (net (code "42") (name "RES") (class "Default")
      (node (ref "C10") (pin "1") (pinfunction "1_1") (pintype "passive"))
      (node (ref "OLED") (pin "P$9") (pinfunction "9.RES_P$9") (pintype "bidirectional"))
      (node (ref "R5") (pin "1") (pinfunction "1_1") (pintype "passive"))
    )
    (net (code "43") (name "RST") (class "Default")
      (node (ref "CPU") (pin "RESET") (pinfunction "RESET_RESET") (pintype "bidirectional"))
      (node (ref "RESET") (pin "2") (pinfunction "2_2") (pintype "bidirectional"))
    )
    (net (code "44") (name "RXD") (class "Default")
      (node (ref "CPU") (pin "RXD0") (pinfunction "RX_RXD0") (pintype "bidirectional"))
      (node (ref "USB-SERIAL") (pin "3") (pinfunction "RXD_3") (pintype "bidirectional"))
    )
    (net (code "45") (name "SCL") (class "Default")
      (node (ref "CPU") (pin "GPIO4") (pinfunction "GPIO4_GPIO4") (pintype "bidirectional"))
      (node (ref "OLED") (pin "P$10") (pinfunction "10.SCL_P$10") (pintype "bidirectional"))
      (node (ref "R10") (pin "2") (pinfunction "2_2") (pintype "passive"))
    )
    (net (code "46") (name "SDA") (class "Default")
      (node (ref "CPU") (pin "GPIO5") (pinfunction "GPIO5_GPIO5") (pintype "bidirectional"))
      (node (ref "OLED") (pin "P$11") (pinfunction "11.SDA_P$11") (pintype "bidirectional"))
      (node (ref "R9") (pin "1") (pinfunction "1_1") (pintype "passive"))
    )
    (net (code "47") (name "SPK+") (class "Default")
      (node (ref "JACK") (pin "7") (pinfunction "2S_7") (pintype "bidirectional"))
      (node (ref "SPEAKER") (pin "2") (pinfunction "2_2") (pintype "passive"))
    )
    (net (code "48") (name "SPK-") (class "Default")
      (node (ref "JACK") (pin "5") (pinfunction "3S_5") (pintype "bidirectional"))
      (node (ref "SPEAKER") (pin "1") (pinfunction "1_1") (pintype "passive"))
    )
    (net (code "49") (name "STAT") (class "Default")
      (node (ref "CHG") (pin "1") (pinfunction "CHG_1") (pintype "bidirectional"))
      (node (ref "D1") (pin "+") (pinfunction "+_+") (pintype "passive"))
    )
    (net (code "50") (name "TXD") (class "Default")
      (node (ref "CPU") (pin "TXD0") (pinfunction "TX_TXD0") (pintype "bidirectional"))
      (node (ref "USB-SERIAL") (pin "2") (pinfunction "TXD_2") (pintype "bidirectional"))
    )
    (net (code "51") (name "V3") (class "Default")
      (node (ref "C15") (pin "2") (pinfunction "2_2") (pintype "passive"))
      (node (ref "USB-SERIAL") (pin "4") (pinfunction "V3_4") (pintype "bidirectional"))
    )
    (net (code "52") (name "VBAT") (class "Default")
      (node (ref "BATT") (pin "1") (pinfunction "1_1") (pintype "passive"))
      (node (ref "C18") (pin "2") (pinfunction "2_2") (pintype "passive"))
      (node (ref "C2") (pin "2") (pinfunction "2_2") (pintype "passive"))
      (node (ref "C34") (pin "1") (pinfunction "1_1") (pintype "passive"))
      (node (ref "CHG") (pin "3") (pinfunction "BAT_3") (pintype "bidirectional"))
      (node (ref "LDO1") (pin "3") (pinfunction "IN_3") (pintype "bidirectional"))
      (node (ref "OUTPUT") (pin "6") (pinfunction "VDD_6") (pintype "bidirectional"))
    )
    (net (code "53") (name "VBUS") (class "Default")
      (node (ref "C14") (pin "2") (pinfunction "2_2") (pintype "passive"))
      (node (ref "C16") (pin "2") (pinfunction "2_2") (pintype "passive"))
      (node (ref "CHG") (pin "4") (pinfunction "VBUS_4") (pintype "bidirectional"))
      (node (ref "D2") (pin "+") (pinfunction "+_+") (pintype "passive"))
      (node (ref "USB") (pin "1") (pinfunction "VCC_1") (pintype "bidirectional"))
      (node (ref "USB-SERIAL") (pin "16") (pinfunction "VCC_16") (pintype "bidirectional"))
    )
    (net (code "54") (name "VGND") (class "Default")
      (node (ref "C26") (pin "1") (pinfunction "1_1") (pintype "passive"))
      (node (ref "R11") (pin "1") (pinfunction "1_1") (pintype "passive"))
      (node (ref "R18") (pin "2") (pinfunction "2_2") (pintype "passive"))
      (node (ref "R23") (pin "1") (pinfunction "1_1") (pintype "passive"))
    )
    (net (code "55") (name "VIN") (class "Default")
      (node (ref "C24") (pin "1") (pinfunction "1_1") (pintype "passive"))
      (node (ref "D2") (pin "-") (pinfunction "-_-") (pintype "passive"))
      (node (ref "LDO2") (pin "3") (pinfunction "IN_3") (pintype "bidirectional"))
    )
    (net (code "56") (name "XI") (class "Default")
      (node (ref "C6") (pin "2") (pinfunction "2_2") (pintype "passive"))
      (node (ref "USB-SERIAL") (pin "7") (pinfunction "XI_7") (pintype "bidirectional"))
      (node (ref "X1") (pin "1") (pinfunction "1_1") (pintype "passive"))
    )
    (net (code "57") (name "XO") (class "Default")
      (node (ref "C13") (pin "2") (pinfunction "2_2") (pintype "passive"))
      (node (ref "USB-SERIAL") (pin "8") (pinfunction "XO_8") (pintype "bidirectional"))
      (node (ref "X1") (pin "3") (pinfunction "2_3") (pintype "passive"))
    )
    (net (code "58") (name "unconnected-(CPU-*GPIO9-PadGPIO9)") (class "Default")
      (node (ref "CPU") (pin "GPIO9") (pinfunction "*GPIO9_GPIO9") (pintype "bidirectional"))
    )
    (net (code "59") (name "unconnected-(CPU-*GPIO10-PadGPIO10)") (class "Default")
      (node (ref "CPU") (pin "GPIO10") (pinfunction "*GPIO10_GPIO10") (pintype "bidirectional"))
    )
    (net (code "60") (name "unconnected-(CPU-PadCS0)") (class "Default")
      (node (ref "CPU") (pin "CS0") (pinfunction "CS0_CS0") (pintype "bidirectional"))
    )
    (net (code "61") (name "unconnected-(CPU-PadMISO)") (class "Default")
      (node (ref "CPU") (pin "MISO") (pinfunction "MISO_MISO") (pintype "bidirectional"))
    )
    (net (code "62") (name "unconnected-(CPU-PadMOSI)") (class "Default")
      (node (ref "CPU") (pin "MOSI") (pinfunction "MOSI_MOSI") (pintype "bidirectional"))
    )
    (net (code "63") (name "unconnected-(CPU-PadSCLK)") (class "Default")
      (node (ref "CPU") (pin "SCLK") (pinfunction "SCLK_SCLK") (pintype "bidirectional"))
    )
    (net (code "64") (name "unconnected-(OLED-6.NC-PadP$6)") (class "Default")
      (node (ref "OLED") (pin "P$6") (pinfunction "6.NC_P$6") (pintype "bidirectional"))
    )
    (net (code "65") (name "unconnected-(USB-ID-Pad4)") (class "Default")
      (node (ref "USB") (pin "4") (pinfunction "ID_4") (pintype "bidirectional"))
    )
    (net (code "66") (name "unconnected-(USB-SERIAL-CTS-Pad9)") (class "Default")
      (node (ref "USB-SERIAL") (pin "9") (pinfunction "CTS_9") (pintype "bidirectional"))
    )
    (net (code "67") (name "unconnected-(USB-SERIAL-DCD-Pad12)") (class "Default")
      (node (ref "USB-SERIAL") (pin "12") (pinfunction "DCD_12") (pintype "bidirectional"))
    )
    (net (code "68") (name "unconnected-(USB-SERIAL-DSR-Pad10)") (class "Default")
      (node (ref "USB-SERIAL") (pin "10") (pinfunction "DSR_10") (pintype "bidirectional"))
    )
    (net (code "69") (name "unconnected-(USB-SERIAL-R232-Pad15)") (class "Default")
      (node (ref "USB-SERIAL") (pin "15") (pinfunction "R232_15") (pintype "bidirectional"))
    )
    (net (code "70") (name "unconnected-(USB-SERIAL-RI-Pad11)") (class "Default")
      (node (ref "USB-SERIAL") (pin "11") (pinfunction "RI_11") (pintype "bidirectional"))
    )
    (net (code "71") (name "unconnected-(USB-SERIAL-RTS-Pad14)") (class "Default")
      (node (ref "USB-SERIAL") (pin "14") (pinfunction "RTS_14") (pintype "bidirectional"))
    )
  )
)
